# etch-a-sketch.net
KiCad netlist of a schematic drawn in EAGLE
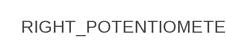
[diagram p0: schematic, sheet 1, part 1 of 2]
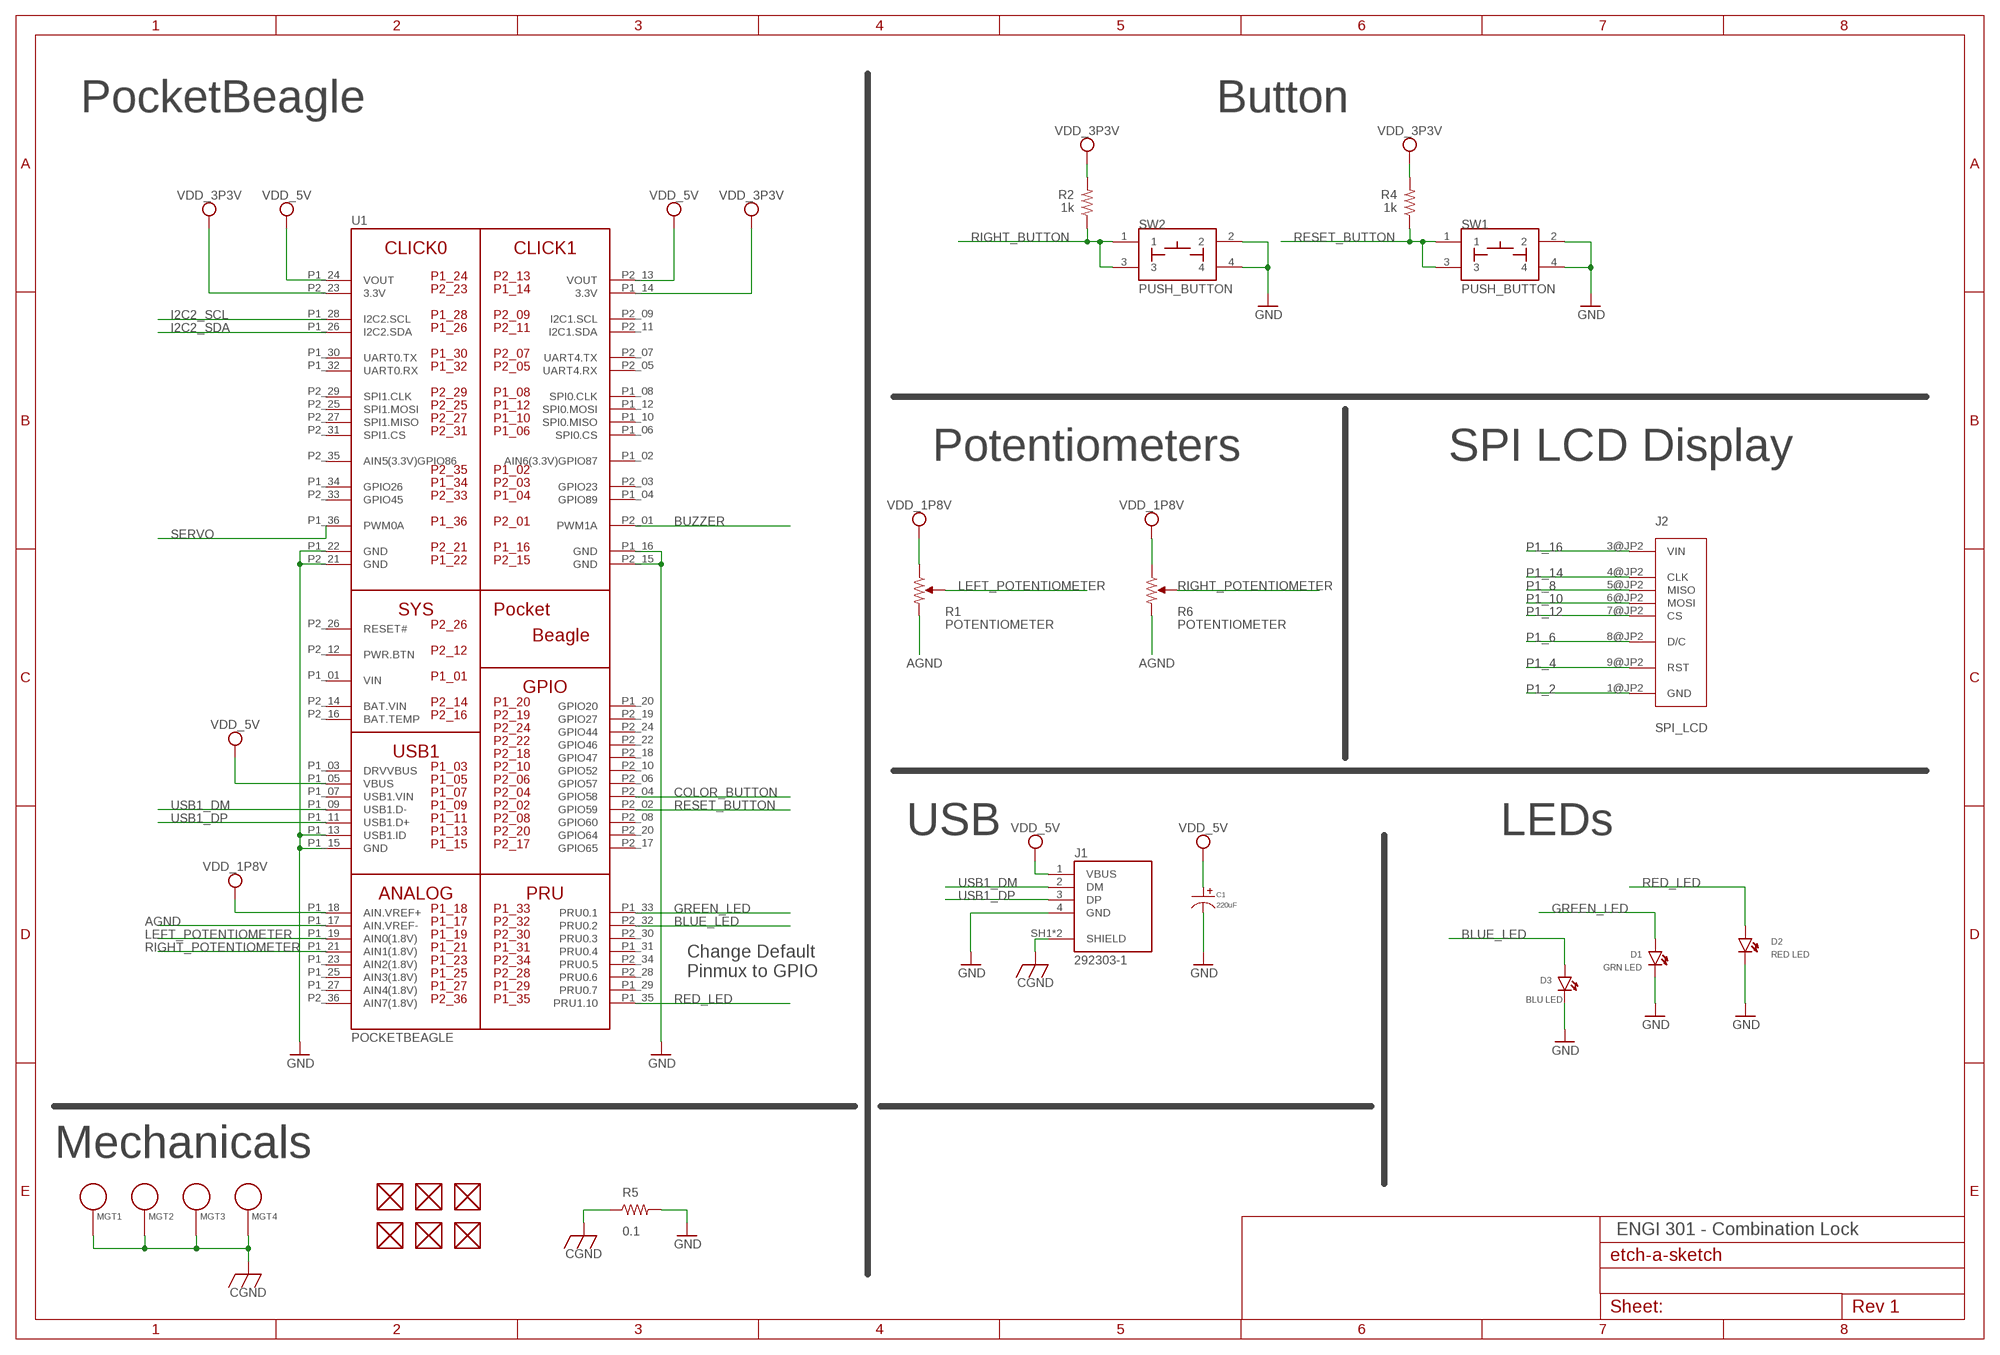
[diagram p1: schematic, sheet 1, part 2 of 2]

(export (version "E")
  (design (tool "Eeschema 10.0.6"))
  (components
    (comp (ref "C1")
      (value "220uF")
      (footprint "eagle-import:CP10MM")
      (libsource (lib "eagle-import") (part "CAPACITOR_P_10MM"))
    )
    (comp (ref "D1")
      (value "GRN LED")
      (footprint "eagle-import:EIA-STD")
      (libsource (lib "eagle-import") (part "LED"))
    )
    (comp (ref "D2")
      (value "RED LED")
      (footprint "eagle-import:EIA-STD")
      (libsource (lib "eagle-import") (part "LED"))
    )
    (comp (ref "D3")
      (value "GRN LED")
      (footprint "eagle-import:EIA-STD")
      (libsource (lib "eagle-import") (part "LED"))
    )
    (comp (ref "FUD1")
      (value "FIDUCIAL")
      (footprint "eagle-import:FIDUCIAL_40MIL")
      (libsource (lib "eagle-import") (part "FIDUCIAL"))
    )
    (comp (ref "FUD2")
      (value "FIDUCIAL")
      (footprint "eagle-import:FIDUCIAL_40MIL")
      (libsource (lib "eagle-import") (part "FIDUCIAL"))
    )
    (comp (ref "FUD3")
      (value "FIDUCIAL")
      (footprint "eagle-import:FIDUCIAL_40MIL")
      (libsource (lib "eagle-import") (part "FIDUCIAL"))
    )
    (comp (ref "FUD4")
      (value "FIDUCIAL")
      (footprint "eagle-import:FIDUCIAL_40MIL")
      (libsource (lib "eagle-import") (part "FIDUCIAL"))
    )
    (comp (ref "FUD5")
      (value "FIDUCIAL")
      (footprint "eagle-import:FIDUCIAL_40MIL")
      (libsource (lib "eagle-import") (part "FIDUCIAL"))
    )
    (comp (ref "FUD6")
      (value "FIDUCIAL")
      (footprint "eagle-import:FIDUCIAL_40MIL")
      (libsource (lib "eagle-import") (part "FIDUCIAL"))
    )
    (comp (ref "J1")
      (value "292303-1")
      (footprint "eagle-import:TE_292303-1")
      (fields (field (name "MF") "TE Connectivity"))
      (libsource (lib "eagle-import") (part "292303-1"))
    )
    (comp (ref "J2")
      (value "SPI_LCD")
      (footprint "eagle-import:TFT_LCD_PCB")
      (libsource (lib "eagle-import") (part "SPI_LCD"))
    )
    (comp (ref "MGT1")
      (value "MOUNTING_HOLE")
      (footprint "eagle-import:MOUNTING_HOLE")
      (libsource (lib "eagle-import") (part "MOUNTING_HOLE"))
    )
    (comp (ref "MGT2")
      (value "MOUNTING_HOLE")
      (footprint "eagle-import:MOUNTING_HOLE")
      (libsource (lib "eagle-import") (part "MOUNTING_HOLE"))
    )
    (comp (ref "MGT3")
      (value "MOUNTING_HOLE")
      (footprint "eagle-import:MOUNTING_HOLE")
      (libsource (lib "eagle-import") (part "MOUNTING_HOLE"))
    )
    (comp (ref "MGT4")
      (value "MOUNTING_HOLE")
      (footprint "eagle-import:MOUNTING_HOLE")
      (libsource (lib "eagle-import") (part "MOUNTING_HOLE"))
    )
    (comp (ref "R1")
      (value "POTENTIOMETER")
      (footprint "eagle-import:POT-PO90S")
      (libsource (lib "eagle-import") (part "POTENTIOMETER"))
    )
    (comp (ref "R2")
      (value "1k")
      (footprint "eagle-import:R0603")
      (libsource (lib "eagle-import") (part "R_R0603"))
    )
    (comp (ref "R4")
      (value "1k")
      (footprint "eagle-import:R0603")
      (libsource (lib "eagle-import") (part "R_R0603"))
    )
    (comp (ref "R5")
      (value "0.1")
      (footprint "eagle-import:R0805")
      (libsource (lib "eagle-import") (part "R_R0805"))
    )
    (comp (ref "R6")
      (value "POTENTIOMETER")
      (footprint "eagle-import:POT-PO90S")
      (libsource (lib "eagle-import") (part "POTENTIOMETER"))
    )
    (comp (ref "SW1")
      (value "PUSH_BUTTON")
      (footprint "eagle-import:BUTTON_12.5MM")
      (libsource (lib "eagle-import") (part "PUSH_BUTTON"))
    )
    (comp (ref "SW2")
      (value "PUSH_BUTTON")
      (footprint "eagle-import:BUTTON_12.5MM")
      (libsource (lib "eagle-import") (part "PUSH_BUTTON"))
    )
    (comp (ref "U1")
      (value "POCKETBEAGLE")
      (footprint "eagle-import:POCKETBEAGLE")
      (libsource (lib "eagle-import") (part "POCKETBEAGLE"))
    )
  )
  (nets
    (net (code "1") (name "/AGND") (class "Default")
      (node (ref "R1") (pin "CW") (pinfunction "CW_CW") (pintype "passive"))
      (node (ref "R6") (pin "CW") (pinfunction "CW_CW") (pintype "passive"))
      (node (ref "U1") (pin "P1_17") (pinfunction "AIN.VREF-_P1_17") (pintype "input"))
    )
    (net (code "2") (name "/BAT.VIN") (class "Default")
      (node (ref "U1") (pin "P2_14") (pinfunction "BAT.VIN_P2_14") (pintype "power_in"))
    )
    (net (code "3") (name "/BUZZER") (class "Default")
      (node (ref "U1") (pin "P2_01") (pinfunction "PWM1A_P2_01") (pintype "bidirectional"))
    )
    (net (code "4") (name "/GREEN_LED") (class "Default")
      (node (ref "D1") (pin "ANODE") (pinfunction "ANODE_ANODE") (pintype "bidirectional"))
      (node (ref "D3") (pin "ANODE") (pinfunction "ANODE_ANODE") (pintype "bidirectional"))
      (node (ref "U1") (pin "P1_33") (pinfunction "PRU0.1_P1_33") (pintype "bidirectional"))
    )
    (net (code "5") (name "/I2C2_SCL") (class "Default")
      (node (ref "U1") (pin "P1_28") (pinfunction "I2C2.SCL_P1_28") (pintype "bidirectional"))
    )
    (net (code "6") (name "/I2C2_SDA") (class "Default")
      (node (ref "U1") (pin "P1_26") (pinfunction "I2C2.SDA_P1_26") (pintype "bidirectional"))
    )
    (net (code "7") (name "/LEFT_POTENTIOMETER") (class "Default")
      (node (ref "R1") (pin "S") (pinfunction "S_S") (pintype "bidirectional"))
      (node (ref "R6") (pin "S") (pinfunction "S_S") (pintype "bidirectional"))
      (node (ref "U1") (pin "P1_19") (pinfunction "AIN0(1.8V)_P1_19") (pintype "input"))
    )
    (net (code "8") (name "/RED_LED") (class "Default")
      (node (ref "D2") (pin "ANODE") (pinfunction "ANODE_ANODE") (pintype "bidirectional"))
      (node (ref "U1") (pin "P1_35") (pinfunction "PRU1.10_P1_35") (pintype "bidirectional"))
    )
    (net (code "9") (name "/RESET_BUTTON") (class "Default")
      (node (ref "R2") (pin "1") (pinfunction "1_1") (pintype "passive"))
      (node (ref "R4") (pin "1") (pinfunction "1_1") (pintype "passive"))
      (node (ref "SW1") (pin "1") (pinfunction "1_1") (pintype "bidirectional"))
      (node (ref "SW1") (pin "3") (pinfunction "3_3") (pintype "bidirectional"))
      (node (ref "SW2") (pin "1") (pinfunction "1_1") (pintype "bidirectional"))
      (node (ref "SW2") (pin "3") (pinfunction "3_3") (pintype "bidirectional"))
      (node (ref "U1") (pin "P2_02") (pinfunction "GPIO59_P2_02") (pintype "bidirectional"))
    )
    (net (code "10") (name "/SERVO") (class "Default")
      (node (ref "U1") (pin "P1_36") (pinfunction "PWM0A_P1_36") (pintype "bidirectional"))
    )
    (net (code "11") (name "/USB1_DM") (class "Default")
      (node (ref "J1") (pin "2") (pinfunction "DM_2") (pintype "passive"))
      (node (ref "U1") (pin "P1_09") (pinfunction "USB1.D-_P1_09") (pintype "bidirectional"))
    )
    (net (code "12") (name "/USB1_DP") (class "Default")
      (node (ref "J1") (pin "3") (pinfunction "DP_3") (pintype "passive"))
      (node (ref "U1") (pin "P1_11") (pinfunction "USB1.D+_P1_11") (pintype "bidirectional"))
    )
    (net (code "13") (name "/VIN") (class "Default")
      (node (ref "U1") (pin "P1_01") (pinfunction "VIN_P1_01") (pintype "power_in"))
    )
    (net (code "14") (name "CGND") (class "Default")
      (node (ref "J1") (pin "SH1") (pinfunction "SHIELD_SH1") (pintype "passive"))
      (node (ref "J1") (pin "SH2") (pinfunction "SHIELD_SH2") (pintype "passive"))
      (node (ref "MGT1") (pin "P$1") (pinfunction "P$1_P$1") (pintype "bidirectional"))
      (node (ref "MGT2") (pin "P$1") (pinfunction "P$1_P$1") (pintype "bidirectional"))
      (node (ref "MGT3") (pin "P$1") (pinfunction "P$1_P$1") (pintype "bidirectional"))
      (node (ref "MGT4") (pin "P$1") (pinfunction "P$1_P$1") (pintype "bidirectional"))
      (node (ref "R5") (pin "1") (pinfunction "1_1") (pintype "passive"))
    )
    (net (code "15") (name "GND") (class "Default")
      (node (ref "C1") (pin "P$2") (pinfunction "P$2_P$2") (pintype "passive"))
      (node (ref "D1") (pin "CATHODE") (pinfunction "CATHODE_CATHODE") (pintype "bidirectional"))
      (node (ref "D2") (pin "CATHODE") (pinfunction "CATHODE_CATHODE") (pintype "bidirectional"))
      (node (ref "D3") (pin "CATHODE") (pinfunction "CATHODE_CATHODE") (pintype "bidirectional"))
      (node (ref "J1") (pin "4") (pinfunction "GND_4") (pintype "passive"))
      (node (ref "R5") (pin "2") (pinfunction "2_2") (pintype "passive"))
      (node (ref "SW1") (pin "2") (pinfunction "2_2") (pintype "bidirectional"))
      (node (ref "SW1") (pin "4") (pinfunction "4_4") (pintype "bidirectional"))
      (node (ref "SW2") (pin "2") (pinfunction "2_2") (pintype "bidirectional"))
      (node (ref "SW2") (pin "4") (pinfunction "4_4") (pintype "bidirectional"))
      (node (ref "U1") (pin "P1_13") (pinfunction "USB1.ID_P1_13") (pintype "bidirectional"))
      (node (ref "U1") (pin "P1_15") (pinfunction "GND_P1_15") (pintype "bidirectional"))
      (node (ref "U1") (pin "P1_16") (pinfunction "GND_P1_16") (pintype "power_in"))
      (node (ref "U1") (pin "P1_22") (pinfunction "GND_P1_22") (pintype "power_in"))
      (node (ref "U1") (pin "P2_15") (pinfunction "GND_P2_15") (pintype "power_in"))
      (node (ref "U1") (pin "P2_21") (pinfunction "GND_P2_21") (pintype "power_in"))
    )
    (net (code "16") (name "VDD_1P8V") (class "Default")
      (node (ref "R1") (pin "CCW") (pinfunction "CCW_CCW") (pintype "passive"))
      (node (ref "R6") (pin "CCW") (pinfunction "CCW_CCW") (pintype "passive"))
      (node (ref "U1") (pin "P1_18") (pinfunction "AIN.VREF+_P1_18") (pintype "input"))
    )
    (net (code "17") (name "VDD_3P3V") (class "Default")
      (node (ref "R2") (pin "2") (pinfunction "2_2") (pintype "passive"))
      (node (ref "R4") (pin "2") (pinfunction "2_2") (pintype "passive"))
      (node (ref "U1") (pin "P1_14") (pinfunction "3.3V_P1_14") (pintype "power_in"))
      (node (ref "U1") (pin "P2_23") (pinfunction "3.3V_P2_23") (pintype "power_in"))
    )
    (net (code "18") (name "VDD_5V") (class "Default")
      (node (ref "C1") (pin "P$1") (pinfunction "P$1_P$1") (pintype "passive"))
      (node (ref "J1") (pin "1") (pinfunction "VBUS_1") (pintype "passive"))
      (node (ref "U1") (pin "P1_05") (pinfunction "VBUS_P1_05") (pintype "bidirectional"))
      (node (ref "U1") (pin "P1_24") (pinfunction "VOUT_P1_24") (pintype "power_in"))
      (node (ref "U1") (pin "P2_13") (pinfunction "VOUT_P2_13") (pintype "power_in"))
    )
    (net (code "19") (name "unconnected-(FUD1-PadP$1)") (class "Default")
      (node (ref "FUD1") (pin "P$1") (pinfunction "P$1_P$1") (pintype "no_connect"))
    )
    (net (code "20") (name "unconnected-(FUD2-PadP$1)") (class "Default")
      (node (ref "FUD2") (pin "P$1") (pinfunction "P$1_P$1") (pintype "no_connect"))
    )
    (net (code "21") (name "unconnected-(FUD3-PadP$1)") (class "Default")
      (node (ref "FUD3") (pin "P$1") (pinfunction "P$1_P$1") (pintype "no_connect"))
    )
    (net (code "22") (name "unconnected-(FUD4-PadP$1)") (class "Default")
      (node (ref "FUD4") (pin "P$1") (pinfunction "P$1_P$1") (pintype "no_connect"))
    )
    (net (code "23") (name "unconnected-(FUD5-PadP$1)") (class "Default")
      (node (ref "FUD5") (pin "P$1") (pinfunction "P$1_P$1") (pintype "no_connect"))
    )
    (net (code "24") (name "unconnected-(FUD6-PadP$1)") (class "Default")
      (node (ref "FUD6") (pin "P$1") (pinfunction "P$1_P$1") (pintype "no_connect"))
    )
    (net (code "25") (name "unconnected-(J2-CLK-Pad4@JP2)") (class "Default")
      (node (ref "J2") (pin "4@JP2") (pinfunction "CLK_4@JP2") (pintype "bidirectional"))
    )
    (net (code "26") (name "unconnected-(J2-CS-Pad7@JP2)") (class "Default")
      (node (ref "J2") (pin "7@JP2") (pinfunction "CS_7@JP2") (pintype "bidirectional"))
    )
    (net (code "27") (name "unconnected-(J2-D{slash}C-Pad8@JP2)") (class "Default")
      (node (ref "J2") (pin "8@JP2") (pinfunction "D/C_8@JP2") (pintype "bidirectional"))
    )
    (net (code "28") (name "unconnected-(J2-GND-Pad1@JP2)") (class "Default")
      (node (ref "J2") (pin "1@JP2") (pinfunction "GND_1@JP2") (pintype "bidirectional"))
    )
    (net (code "29") (name "unconnected-(J2-MISO-Pad5@JP2)") (class "Default")
      (node (ref "J2") (pin "5@JP2") (pinfunction "MISO_5@JP2") (pintype "bidirectional"))
    )
    (net (code "30") (name "unconnected-(J2-MOSI-Pad6@JP2)") (class "Default")
      (node (ref "J2") (pin "6@JP2") (pinfunction "MOSI_6@JP2") (pintype "bidirectional"))
    )
    (net (code "31") (name "unconnected-(J2-RST-Pad9@JP2)") (class "Default")
      (node (ref "J2") (pin "9@JP2") (pinfunction "RST_9@JP2") (pintype "bidirectional"))
    )
    (net (code "32") (name "unconnected-(J2-VIN-Pad3@JP2)") (class "Default")
      (node (ref "J2") (pin "3@JP2") (pinfunction "VIN_3@JP2") (pintype "bidirectional"))
    )
    (net (code "33") (name "unconnected-(U1-AIN1(1.8V)-PadP1_21)") (class "Default")
      (node (ref "U1") (pin "P1_21") (pinfunction "AIN1(1.8V)_P1_21") (pintype "input"))
    )
    (net (code "34") (name "unconnected-(U1-AIN2(1.8V)-PadP1_23)") (class "Default")
      (node (ref "U1") (pin "P1_23") (pinfunction "AIN2(1.8V)_P1_23") (pintype "input"))
    )
    (net (code "35") (name "unconnected-(U1-AIN3(1.8V)-PadP1_25)") (class "Default")
      (node (ref "U1") (pin "P1_25") (pinfunction "AIN3(1.8V)_P1_25") (pintype "input"))
    )
    (net (code "36") (name "unconnected-(U1-AIN4(1.8V)-PadP1_27)") (class "Default")
      (node (ref "U1") (pin "P1_27") (pinfunction "AIN4(1.8V)_P1_27") (pintype "input"))
    )
    (net (code "37") (name "unconnected-(U1-AIN5(3.3V)GPIO86-PadP2_35)") (class "Default")
      (node (ref "U1") (pin "P2_35") (pinfunction "AIN5(3.3V)GPIO86_P2_35") (pintype "bidirectional"))
    )
    (net (code "38") (name "unconnected-(U1-AIN6(3.3V)GPIO87-PadP1_02)") (class "Default")
      (node (ref "U1") (pin "P1_02") (pinfunction "AIN6(3.3V)GPIO87_P1_02") (pintype "bidirectional"))
    )
    (net (code "39") (name "unconnected-(U1-AIN7(1.8V)-PadP2_36)") (class "Default")
      (node (ref "U1") (pin "P2_36") (pinfunction "AIN7(1.8V)_P2_36") (pintype "input"))
    )
    (net (code "40") (name "unconnected-(U1-BAT.TEMP-PadP2_16)") (class "Default")
      (node (ref "U1") (pin "P2_16") (pinfunction "BAT.TEMP_P2_16") (pintype "input"))
    )
    (net (code "41") (name "unconnected-(U1-DRVVBUS-PadP1_03)") (class "Default")
      (node (ref "U1") (pin "P1_03") (pinfunction "DRVVBUS_P1_03") (pintype "bidirectional"))
    )
    (net (code "42") (name "unconnected-(U1-GPIO20-PadP1_20)") (class "Default")
      (node (ref "U1") (pin "P1_20") (pinfunction "GPIO20_P1_20") (pintype "bidirectional"))
    )
    (net (code "43") (name "unconnected-(U1-GPIO23-PadP2_03)") (class "Default")
      (node (ref "U1") (pin "P2_03") (pinfunction "GPIO23_P2_03") (pintype "bidirectional"))
    )
    (net (code "44") (name "unconnected-(U1-GPIO26-PadP1_34)") (class "Default")
      (node (ref "U1") (pin "P1_34") (pinfunction "GPIO26_P1_34") (pintype "bidirectional"))
    )
    (net (code "45") (name "unconnected-(U1-GPIO27-PadP2_19)") (class "Default")
      (node (ref "U1") (pin "P2_19") (pinfunction "GPIO27_P2_19") (pintype "bidirectional"))
    )
    (net (code "46") (name "unconnected-(U1-GPIO44-PadP2_24)") (class "Default")
      (node (ref "U1") (pin "P2_24") (pinfunction "GPIO44_P2_24") (pintype "bidirectional"))
    )
    (net (code "47") (name "unconnected-(U1-GPIO45-PadP2_33)") (class "Default")
      (node (ref "U1") (pin "P2_33") (pinfunction "GPIO45_P2_33") (pintype "bidirectional"))
    )
    (net (code "48") (name "unconnected-(U1-GPIO46-PadP2_22)") (class "Default")
      (node (ref "U1") (pin "P2_22") (pinfunction "GPIO46_P2_22") (pintype "bidirectional"))
    )
    (net (code "49") (name "unconnected-(U1-GPIO47-PadP2_18)") (class "Default")
      (node (ref "U1") (pin "P2_18") (pinfunction "GPIO47_P2_18") (pintype "bidirectional"))
    )
    (net (code "50") (name "unconnected-(U1-GPIO52-PadP2_10)") (class "Default")
      (node (ref "U1") (pin "P2_10") (pinfunction "GPIO52_P2_10") (pintype "bidirectional"))
    )
    (net (code "51") (name "unconnected-(U1-GPIO57-PadP2_06)") (class "Default")
      (node (ref "U1") (pin "P2_06") (pinfunction "GPIO57_P2_06") (pintype "bidirectional"))
    )
    (net (code "52") (name "unconnected-(U1-GPIO58-PadP2_04)") (class "Default")
      (node (ref "U1") (pin "P2_04") (pinfunction "GPIO58_P2_04") (pintype "bidirectional"))
    )
    (net (code "53") (name "unconnected-(U1-GPIO60-PadP2_08)") (class "Default")
      (node (ref "U1") (pin "P2_08") (pinfunction "GPIO60_P2_08") (pintype "bidirectional"))
    )
    (net (code "54") (name "unconnected-(U1-GPIO64-PadP2_20)") (class "Default")
      (node (ref "U1") (pin "P2_20") (pinfunction "GPIO64_P2_20") (pintype "bidirectional"))
    )
    (net (code "55") (name "unconnected-(U1-GPIO65-PadP2_17)") (class "Default")
      (node (ref "U1") (pin "P2_17") (pinfunction "GPIO65_P2_17") (pintype "bidirectional"))
    )
    (net (code "56") (name "unconnected-(U1-GPIO89-PadP1_04)") (class "Default")
      (node (ref "U1") (pin "P1_04") (pinfunction "GPIO89_P1_04") (pintype "bidirectional"))
    )
    (net (code "57") (name "unconnected-(U1-I2C1.SCL-PadP2_09)") (class "Default")
      (node (ref "U1") (pin "P2_09") (pinfunction "I2C1.SCL_P2_09") (pintype "bidirectional"))
    )
    (net (code "58") (name "unconnected-(U1-I2C1.SDA-PadP2_11)") (class "Default")
      (node (ref "U1") (pin "P2_11") (pinfunction "I2C1.SDA_P2_11") (pintype "bidirectional"))
    )
    (net (code "59") (name "unconnected-(U1-PRU0.2-PadP2_32)") (class "Default")
      (node (ref "U1") (pin "P2_32") (pinfunction "PRU0.2_P2_32") (pintype "bidirectional"))
    )
    (net (code "60") (name "unconnected-(U1-PRU0.3-PadP2_30)") (class "Default")
      (node (ref "U1") (pin "P2_30") (pinfunction "PRU0.3_P2_30") (pintype "bidirectional"))
    )
    (net (code "61") (name "unconnected-(U1-PRU0.4-PadP1_31)") (class "Default")
      (node (ref "U1") (pin "P1_31") (pinfunction "PRU0.4_P1_31") (pintype "bidirectional"))
    )
    (net (code "62") (name "unconnected-(U1-PRU0.5-PadP2_34)") (class "Default")
      (node (ref "U1") (pin "P2_34") (pinfunction "PRU0.5_P2_34") (pintype "bidirectional"))
    )
    (net (code "63") (name "unconnected-(U1-PRU0.6-PadP2_28)") (class "Default")
      (node (ref "U1") (pin "P2_28") (pinfunction "PRU0.6_P2_28") (pintype "bidirectional"))
    )
    (net (code "64") (name "unconnected-(U1-PRU0.7-PadP1_29)") (class "Default")
      (node (ref "U1") (pin "P1_29") (pinfunction "PRU0.7_P1_29") (pintype "bidirectional"))
    )
    (net (code "65") (name "unconnected-(U1-PWR.BTN-PadP2_12)") (class "Default")
      (node (ref "U1") (pin "P2_12") (pinfunction "PWR.BTN_P2_12") (pintype "input"))
    )
    (net (code "66") (name "unconnected-(U1-RESET#-PadP2_26)") (class "Default")
      (node (ref "U1") (pin "P2_26") (pinfunction "RESET#_P2_26") (pintype "input"))
    )
    (net (code "67") (name "unconnected-(U1-SPI0.CLK-PadP1_08)") (class "Default")
      (node (ref "U1") (pin "P1_08") (pinfunction "SPI0.CLK_P1_08") (pintype "bidirectional"))
    )
    (net (code "68") (name "unconnected-(U1-SPI0.CS-PadP1_06)") (class "Default")
      (node (ref "U1") (pin "P1_06") (pinfunction "SPI0.CS_P1_06") (pintype "bidirectional"))
    )
    (net (code "69") (name "unconnected-(U1-SPI0.MISO-PadP1_10)") (class "Default")
      (node (ref "U1") (pin "P1_10") (pinfunction "SPI0.MISO_P1_10") (pintype "bidirectional"))
    )
    (net (code "70") (name "unconnected-(U1-SPI0.MOSI-PadP1_12)") (class "Default")
      (node (ref "U1") (pin "P1_12") (pinfunction "SPI0.MOSI_P1_12") (pintype "bidirectional"))
    )
    (net (code "71") (name "unconnected-(U1-SPI1.CLK-PadP2_29)") (class "Default")
      (node (ref "U1") (pin "P2_29") (pinfunction "SPI1.CLK_P2_29") (pintype "bidirectional"))
    )
    (net (code "72") (name "unconnected-(U1-SPI1.CS-PadP2_31)") (class "Default")
      (node (ref "U1") (pin "P2_31") (pinfunction "SPI1.CS_P2_31") (pintype "bidirectional"))
    )
    (net (code "73") (name "unconnected-(U1-SPI1.MISO-PadP2_27)") (class "Default")
      (node (ref "U1") (pin "P2_27") (pinfunction "SPI1.MISO_P2_27") (pintype "bidirectional"))
    )
    (net (code "74") (name "unconnected-(U1-SPI1.MOSI-PadP2_25)") (class "Default")
      (node (ref "U1") (pin "P2_25") (pinfunction "SPI1.MOSI_P2_25") (pintype "bidirectional"))
    )
    (net (code "75") (name "unconnected-(U1-UART0.RX-PadP1_32)") (class "Default")
      (node (ref "U1") (pin "P1_32") (pinfunction "UART0.RX_P1_32") (pintype "bidirectional"))
    )
    (net (code "76") (name "unconnected-(U1-UART0.TX-PadP1_30)") (class "Default")
      (node (ref "U1") (pin "P1_30") (pinfunction "UART0.TX_P1_30") (pintype "bidirectional"))
    )
    (net (code "77") (name "unconnected-(U1-UART4.RX-PadP2_05)") (class "Default")
      (node (ref "U1") (pin "P2_05") (pinfunction "UART4.RX_P2_05") (pintype "bidirectional"))
    )
    (net (code "78") (name "unconnected-(U1-UART4.TX-PadP2_07)") (class "Default")
      (node (ref "U1") (pin "P2_07") (pinfunction "UART4.TX_P2_07") (pintype "bidirectional"))
    )
    (net (code "79") (name "unconnected-(U1-USB1.VIN-PadP1_07)") (class "Default")
      (node (ref "U1") (pin "P1_07") (pinfunction "USB1.VIN_P1_07") (pintype "bidirectional"))
    )
  )
)
